# 1_Interface_Charge_RBF.net
KiCad netlist of a schematic drawn in Altium Designer
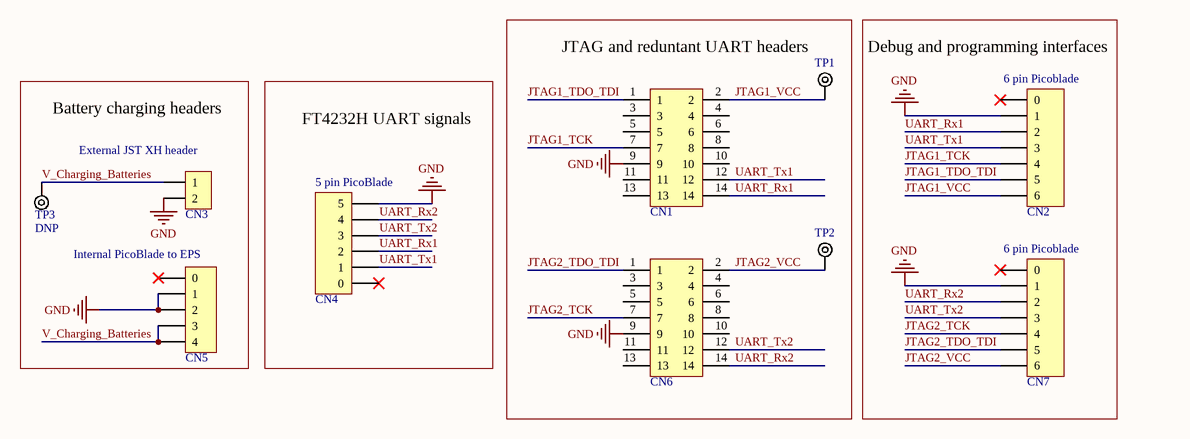
[diagram p0: 1_Interface_Charge_RBF.SchDoc]

(export (version "E")
  (design (tool "Eeschema 10.0.6"))
  (components
    (comp (ref "CN1")
      (value "7 POS dual line Pin Header 2.54mm")
      (footprint "CONN HEADER VERT 14POS 2.54MM")
      (description "Headers & Wire Housings 07+07 DIL VERTICAL PIN HEADER GOLD HT")
      (fields (field (name "MANUFACTURER") "Harwin") (field (name "MANUFACTURER PART NUMBER") "M20-9980745"))
      (libsource (lib "IB_floripasat2") (part "M20-9980745"))
    )
    (comp (ref "CN2")
      (value "6 pin Picoblade")
      (footprint "PICO BLADE 0533980671")
      (description "1.25mm Pitch PicoBlade™ Header, Surface Mount, Vertical, 6 Circuits")
      (fields (field (name "MANUFACTURER") "Molex") (field (name "MANUFACTURER PART NUMBER") "53398-0671"))
      (libsource (lib "IB_floripasat2") (part "53398-0671"))
    )
    (comp (ref "CN3")
      (value "JST 2 position header 2.5mm")
      (footprint "B2B-XH-A-M(LF)(SN)")
      (description "CONN HEADER TOP 2POS 2.5MM GRN")
      (fields
        (field (name "MANUFACTURER") "JST")
        (field (name "MANUFACTURER PART NUMBER") "B2B-XH-A-M(LF)(SN)")
      )
      (libsource (lib "IB_floripasat2") (part "B2B-XH-A-M(LF)(SN)"))
    )
    (comp (ref "CN4")
      (value "5 pin PicoBlade")
      (footprint "PICO BLADE 0533980571")
      (description "Wire-To-Board Connector, Vertical, PicoBlade 53398 Series, Surface Mount, Header, 5, 1.25 mm")
      (fields (field (name "MANUFACTURER") "Molex") (field (name "MANUFACTURER PART NUMBER") "53398-0571"))
      (libsource (lib "IB_floripasat2") (part "53398-0571"))
    )
    (comp (ref "CN5")
      (value "4 pin Picoblade")
      (footprint "PICO BLADE 0533980471")
      (description "Connector Header Surface Mount 4 position 0.049\" (1.25mm)")
      (fields (field (name "MANUFACTURER") "Molex"))
      (libsource (lib "IB_floripasat2") (part "0533980471"))
    )
    (comp (ref "CN6")
      (value "7 POS dual line Pin Header 2.54mm")
      (footprint "CONN HEADER VERT 14POS 2.54MM")
      (description "Headers & Wire Housings 07+07 DIL VERTICAL PIN HEADER GOLD HT")
      (fields (field (name "MANUFACTURER") "Harwin") (field (name "MANUFACTURER PART NUMBER") "M20-9980745"))
      (libsource (lib "IB_floripasat2") (part "M20-9980745"))
    )
    (comp (ref "CN7")
      (value "6 pin Picoblade")
      (footprint "PICO BLADE 0533980671")
      (description "1.25mm Pitch PicoBlade™ Header, Surface Mount, Vertical, 6 Circuits")
      (fields (field (name "MANUFACTURER") "Molex") (field (name "MANUFACTURER PART NUMBER") "53398-0671"))
      (libsource (lib "IB_floripasat2") (part "53398-0671"))
    )
    (comp (ref "TP1")
      (value "DNP")
      (footprint "TEST POINT PTH")
      (description "TEST POINT PAD")
      (libsource (lib "IB_floripasat2") (part "Test Point PTH"))
    )
    (comp (ref "TP2")
      (value "DNP")
      (footprint "TEST POINT PTH")
      (description "TEST POINT PAD")
      (libsource (lib "IB_floripasat2") (part "Test Point PTH"))
    )
    (comp (ref "TP3")
      (value "DNP")
      (footprint "TEST POINT PTH")
      (description "TEST POINT PAD")
      (libsource (lib "IB_floripasat2") (part "Test Point PTH"))
    )
  )
  (nets
    (net (code "1") (name "/JTAG1_TCK") (class "Default")
      (node (ref "CN1") (pin "7") (pinfunction "7_7") (pintype "passive"))
      (node (ref "CN2") (pin "4") (pinfunction "4_4") (pintype "passive"))
    )
    (net (code "2") (name "/JTAG1_TDO_TDI") (class "Default")
      (node (ref "CN1") (pin "1") (pinfunction "1_1") (pintype "passive"))
      (node (ref "CN2") (pin "5") (pinfunction "5_5") (pintype "passive"))
    )
    (net (code "3") (name "/JTAG1_VCC") (class "Default")
      (node (ref "CN1") (pin "2") (pinfunction "2_2") (pintype "passive"))
      (node (ref "CN2") (pin "6") (pinfunction "6_6") (pintype "passive"))
      (node (ref "TP1") (pin "1") (pinfunction "1_1") (pintype "passive"))
    )
    (net (code "4") (name "/JTAG2_TCK") (class "Default")
      (node (ref "CN6") (pin "7") (pinfunction "7_7") (pintype "passive"))
      (node (ref "CN7") (pin "4") (pinfunction "4_4") (pintype "passive"))
    )
    (net (code "5") (name "/JTAG2_TDO_TDI") (class "Default")
      (node (ref "CN6") (pin "1") (pinfunction "1_1") (pintype "passive"))
      (node (ref "CN7") (pin "5") (pinfunction "5_5") (pintype "passive"))
    )
    (net (code "6") (name "/JTAG2_VCC") (class "Default")
      (node (ref "CN6") (pin "2") (pinfunction "2_2") (pintype "passive"))
      (node (ref "CN7") (pin "6") (pinfunction "6_6") (pintype "passive"))
      (node (ref "TP2") (pin "1") (pinfunction "1_1") (pintype "passive"))
    )
    (net (code "7") (name "/UART_Rx1") (class "Default")
      (node (ref "CN1") (pin "14") (pinfunction "14_14") (pintype "passive"))
      (node (ref "CN2") (pin "2") (pinfunction "2_2") (pintype "passive"))
      (node (ref "CN4") (pin "2") (pinfunction "2_2") (pintype "passive"))
    )
    (net (code "8") (name "/UART_Rx2") (class "Default")
      (node (ref "CN4") (pin "4") (pinfunction "4_4") (pintype "passive"))
      (node (ref "CN6") (pin "14") (pinfunction "14_14") (pintype "passive"))
      (node (ref "CN7") (pin "2") (pinfunction "2_2") (pintype "passive"))
    )
    (net (code "9") (name "/UART_Tx1") (class "Default")
      (node (ref "CN1") (pin "12") (pinfunction "12_12") (pintype "passive"))
      (node (ref "CN2") (pin "3") (pinfunction "3_3") (pintype "passive"))
      (node (ref "CN4") (pin "1") (pinfunction "1_1") (pintype "passive"))
    )
    (net (code "10") (name "/UART_Tx2") (class "Default")
      (node (ref "CN4") (pin "3") (pinfunction "3_3") (pintype "passive"))
      (node (ref "CN6") (pin "12") (pinfunction "12_12") (pintype "passive"))
      (node (ref "CN7") (pin "3") (pinfunction "3_3") (pintype "passive"))
    )
    (net (code "11") (name "/V_Charging_Batteries") (class "Default")
      (node (ref "CN3") (pin "1") (pinfunction "1_1") (pintype "passive"))
      (node (ref "CN5") (pin "3") (pinfunction "3_3") (pintype "passive"))
      (node (ref "CN5") (pin "4") (pinfunction "4_4") (pintype "passive"))
      (node (ref "TP3") (pin "1") (pinfunction "1_1") (pintype "passive"))
    )
    (net (code "12") (name "GND") (class "Default")
      (node (ref "CN1") (pin "9") (pinfunction "9_9") (pintype "passive"))
      (node (ref "CN2") (pin "1") (pinfunction "1_1") (pintype "passive"))
      (node (ref "CN3") (pin "2") (pinfunction "2_2") (pintype "passive"))
      (node (ref "CN4") (pin "5") (pinfunction "5_5") (pintype "passive"))
      (node (ref "CN5") (pin "1") (pinfunction "1_1") (pintype "passive"))
      (node (ref "CN5") (pin "2") (pinfunction "2_2") (pintype "passive"))
      (node (ref "CN6") (pin "9") (pinfunction "9_9") (pintype "passive"))
      (node (ref "CN7") (pin "1") (pinfunction "1_1") (pintype "passive"))
    )
    (net (code "13") (name "unconnected-(CN1-Pad3)") (class "Default")
      (node (ref "CN1") (pin "3") (pinfunction "3_3") (pintype "passive"))
    )
    (net (code "14") (name "unconnected-(CN1-Pad4)") (class "Default")
      (node (ref "CN1") (pin "4") (pinfunction "4_4") (pintype "passive"))
    )
    (net (code "15") (name "unconnected-(CN1-Pad5)") (class "Default")
      (node (ref "CN1") (pin "5") (pinfunction "5_5") (pintype "passive"))
    )
    (net (code "16") (name "unconnected-(CN1-Pad6)") (class "Default")
      (node (ref "CN1") (pin "6") (pinfunction "6_6") (pintype "passive"))
    )
    (net (code "17") (name "unconnected-(CN1-Pad8)") (class "Default")
      (node (ref "CN1") (pin "8") (pinfunction "8_8") (pintype "passive"))
    )
    (net (code "18") (name "unconnected-(CN1-Pad10)") (class "Default")
      (node (ref "CN1") (pin "10") (pinfunction "10_10") (pintype "passive"))
    )
    (net (code "19") (name "unconnected-(CN1-Pad11)") (class "Default")
      (node (ref "CN1") (pin "11") (pinfunction "11_11") (pintype "passive"))
    )
    (net (code "20") (name "unconnected-(CN1-Pad13)") (class "Default")
      (node (ref "CN1") (pin "13") (pinfunction "13_13") (pintype "passive"))
    )
    (net (code "21") (name "unconnected-(CN2-Pad0)") (class "Default")
      (node (ref "CN2") (pin "0") (pinfunction "0_0") (pintype "passive+no_connect"))
    )
    (net (code "22") (name "unconnected-(CN4-Pad0)") (class "Default")
      (node (ref "CN4") (pin "0") (pinfunction "0_0") (pintype "passive+no_connect"))
    )
    (net (code "23") (name "unconnected-(CN5-Pad0)") (class "Default")
      (node (ref "CN5") (pin "0") (pinfunction "0_0") (pintype "passive+no_connect"))
    )
    (net (code "24") (name "unconnected-(CN6-Pad3)") (class "Default")
      (node (ref "CN6") (pin "3") (pinfunction "3_3") (pintype "passive"))
    )
    (net (code "25") (name "unconnected-(CN6-Pad4)") (class "Default")
      (node (ref "CN6") (pin "4") (pinfunction "4_4") (pintype "passive"))
    )
    (net (code "26") (name "unconnected-(CN6-Pad5)") (class "Default")
      (node (ref "CN6") (pin "5") (pinfunction "5_5") (pintype "passive"))
    )
    (net (code "27") (name "unconnected-(CN6-Pad6)") (class "Default")
      (node (ref "CN6") (pin "6") (pinfunction "6_6") (pintype "passive"))
    )
    (net (code "28") (name "unconnected-(CN6-Pad8)") (class "Default")
      (node (ref "CN6") (pin "8") (pinfunction "8_8") (pintype "passive"))
    )
    (net (code "29") (name "unconnected-(CN6-Pad10)") (class "Default")
      (node (ref "CN6") (pin "10") (pinfunction "10_10") (pintype "passive"))
    )
    (net (code "30") (name "unconnected-(CN6-Pad11)") (class "Default")
      (node (ref "CN6") (pin "11") (pinfunction "11_11") (pintype "passive"))
    )
    (net (code "31") (name "unconnected-(CN6-Pad13)") (class "Default")
      (node (ref "CN6") (pin "13") (pinfunction "13_13") (pintype "passive"))
    )
    (net (code "32") (name "unconnected-(CN7-Pad0)") (class "Default")
      (node (ref "CN7") (pin "0") (pinfunction "0_0") (pintype "passive+no_connect"))
    )
  )
)
